# optical_encoder.net
KiCad netlist of a schematic drawn in EAGLE
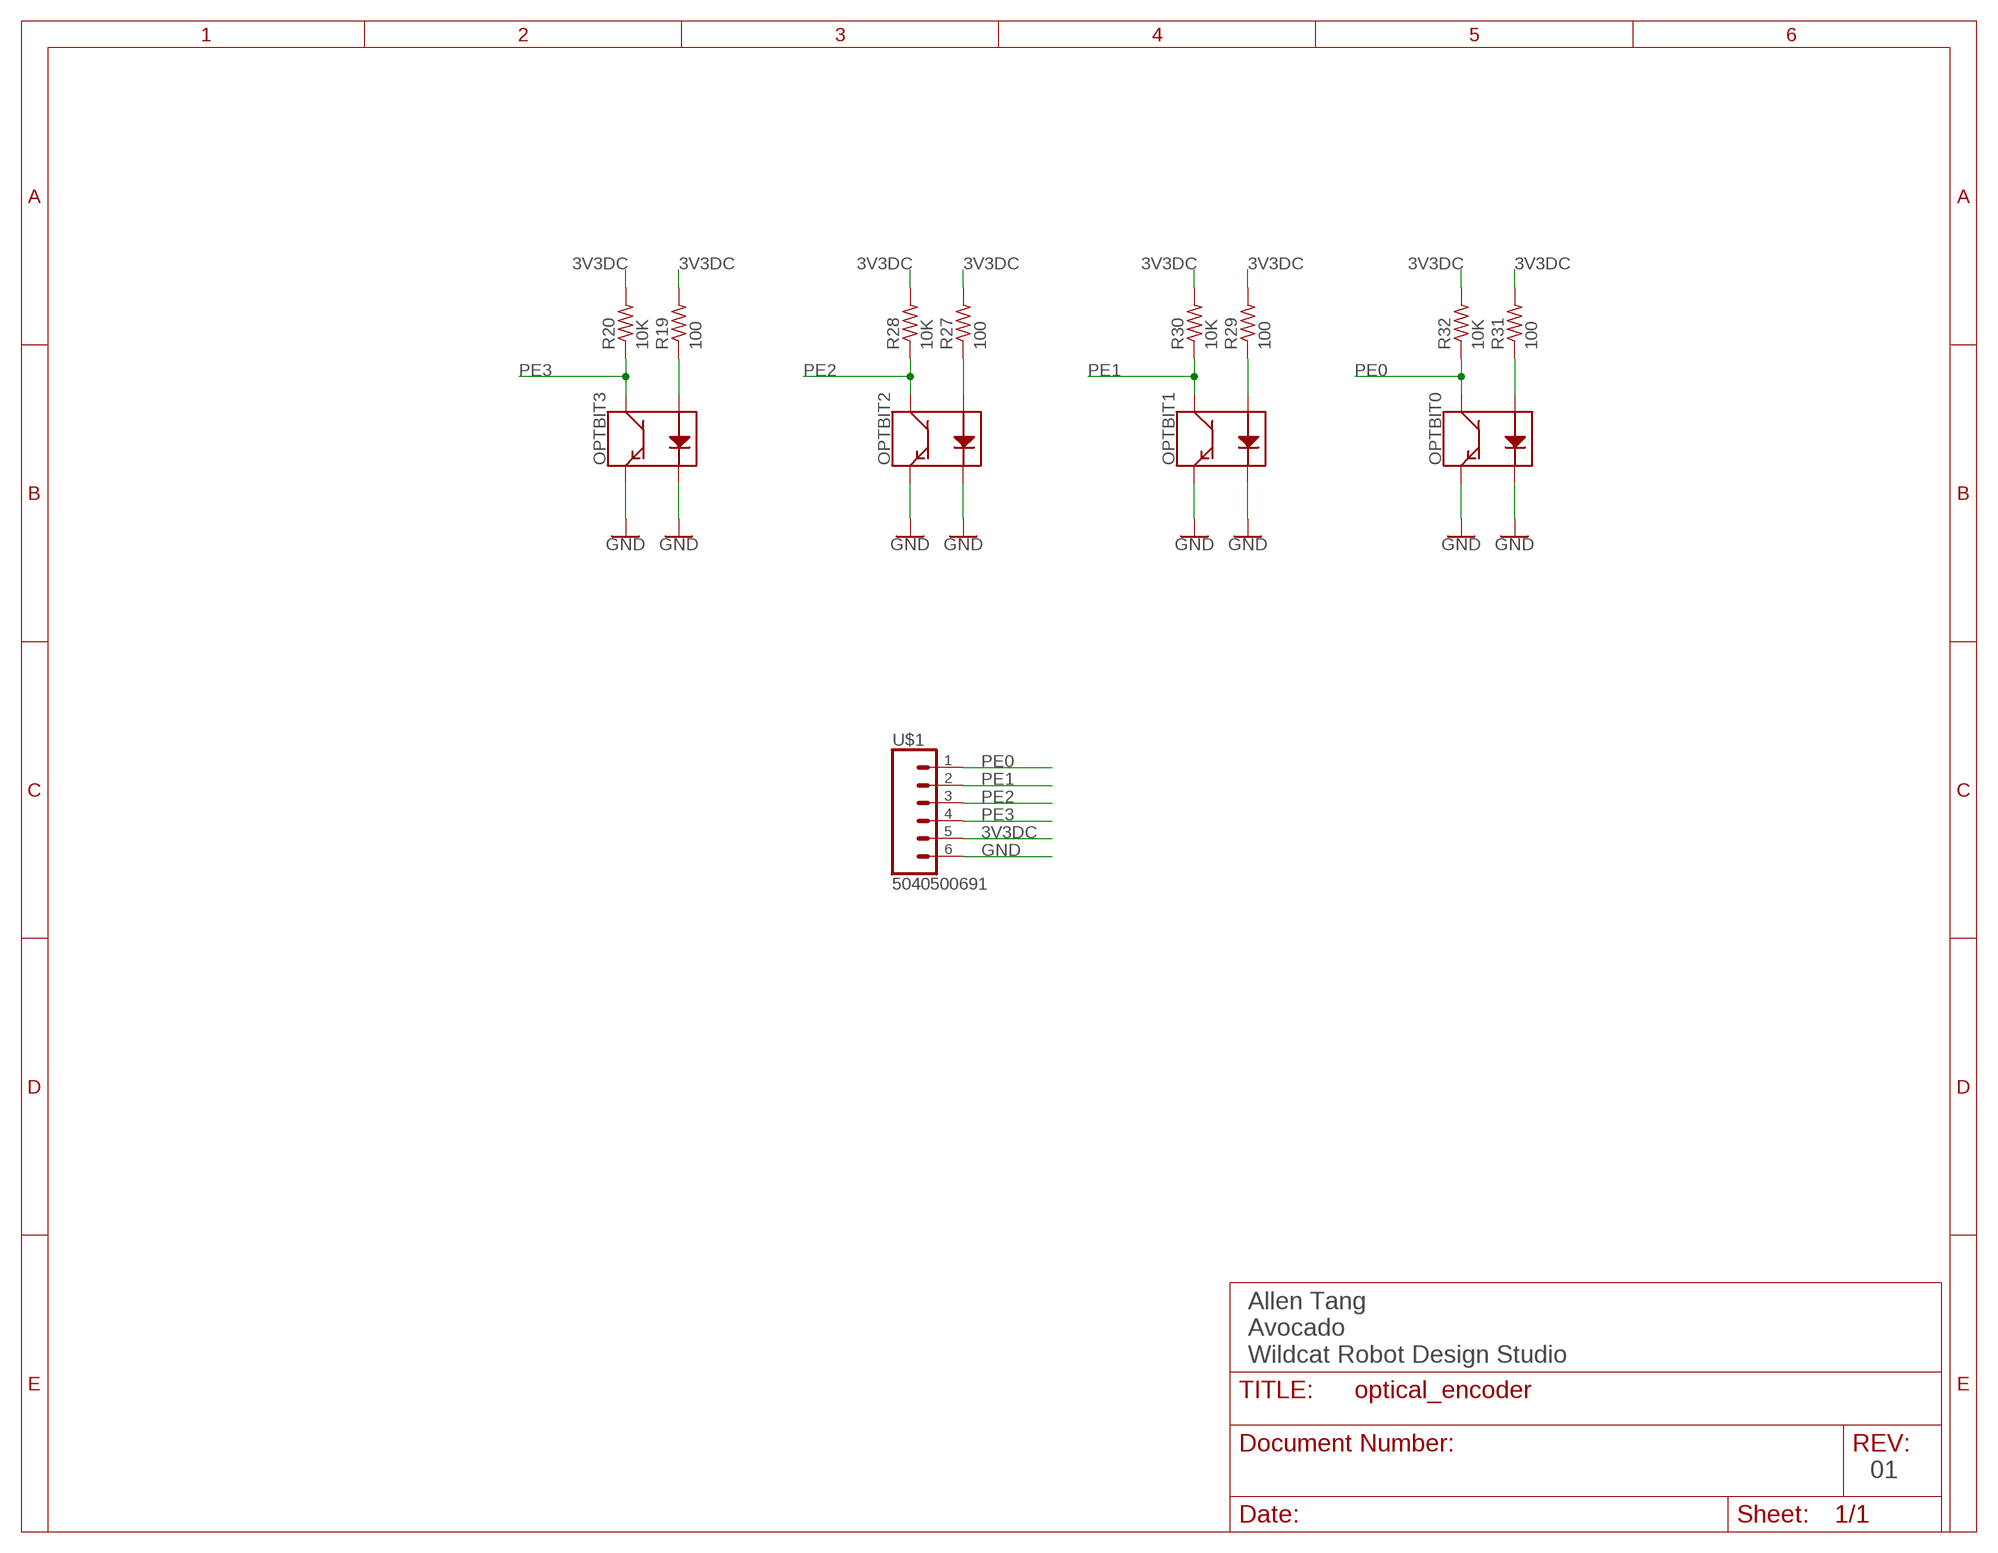
[diagram p0: schematic, sheet 1]

(export (version "E")
  (design (tool "Eeschema 10.0.6"))
  (components
    (comp (ref "OPTBIT0")
      (value "QRE1113")
      (footprint "eagle-import:QRE1113")
      (libsource (lib "eagle-import") (part "QRE1113"))
    )
    (comp (ref "OPTBIT1")
      (value "QRE1113")
      (footprint "eagle-import:QRE1113")
      (libsource (lib "eagle-import") (part "QRE1113"))
    )
    (comp (ref "OPTBIT2")
      (value "QRE1113")
      (footprint "eagle-import:QRE1113")
      (libsource (lib "eagle-import") (part "QRE1113"))
    )
    (comp (ref "OPTBIT3")
      (value "QRE1113")
      (footprint "eagle-import:QRE1113")
      (libsource (lib "eagle-import") (part "QRE1113"))
    )
    (comp (ref "R19")
      (value "100")
      (footprint "eagle-import:R0402")
      (libsource (lib "eagle-import") (part "R-US_R0402"))
    )
    (comp (ref "R20")
      (value "10K")
      (footprint "eagle-import:R0402")
      (libsource (lib "eagle-import") (part "R-US_R0402"))
    )
    (comp (ref "R27")
      (value "100")
      (footprint "eagle-import:R0402")
      (libsource (lib "eagle-import") (part "R-US_R0402"))
    )
    (comp (ref "R28")
      (value "10K")
      (footprint "eagle-import:R0402")
      (libsource (lib "eagle-import") (part "R-US_R0402"))
    )
    (comp (ref "R29")
      (value "100")
      (footprint "eagle-import:R0402")
      (libsource (lib "eagle-import") (part "R-US_R0402"))
    )
    (comp (ref "R30")
      (value "10K")
      (footprint "eagle-import:R0402")
      (libsource (lib "eagle-import") (part "R-US_R0402"))
    )
    (comp (ref "R31")
      (value "100")
      (footprint "eagle-import:R0402")
      (libsource (lib "eagle-import") (part "R-US_R0402"))
    )
    (comp (ref "R32")
      (value "10K")
      (footprint "eagle-import:R0402")
      (libsource (lib "eagle-import") (part "R-US_R0402"))
    )
    (comp (ref "U$1")
      (value "5040500691")
      (footprint "eagle-import:5040500691")
      (libsource (lib "eagle-import") (part "5040500691"))
    )
  )
  (nets
    (net (code "1") (name "/3V3DC") (class "Default")
      (node (ref "R19") (pin "2") (pinfunction "2_2") (pintype "passive"))
      (node (ref "R20") (pin "2") (pinfunction "2_2") (pintype "passive"))
      (node (ref "R27") (pin "2") (pinfunction "2_2") (pintype "passive"))
      (node (ref "R28") (pin "2") (pinfunction "2_2") (pintype "passive"))
      (node (ref "R29") (pin "2") (pinfunction "2_2") (pintype "passive"))
      (node (ref "R30") (pin "2") (pinfunction "2_2") (pintype "passive"))
      (node (ref "R31") (pin "2") (pinfunction "2_2") (pintype "passive"))
      (node (ref "R32") (pin "2") (pinfunction "2_2") (pintype "passive"))
      (node (ref "U$1") (pin "5") (pinfunction "5_5") (pintype "passive"))
    )
    (net (code "2") (name "/PE0") (class "Default")
      (node (ref "OPTBIT0") (pin "3") (pinfunction "C_3") (pintype "bidirectional"))
      (node (ref "R32") (pin "1") (pinfunction "1_1") (pintype "passive"))
      (node (ref "U$1") (pin "1") (pinfunction "1_1") (pintype "passive"))
    )
    (net (code "3") (name "/PE1") (class "Default")
      (node (ref "OPTBIT1") (pin "3") (pinfunction "C_3") (pintype "bidirectional"))
      (node (ref "R30") (pin "1") (pinfunction "1_1") (pintype "passive"))
      (node (ref "U$1") (pin "2") (pinfunction "2_2") (pintype "passive"))
    )
    (net (code "4") (name "/PE2") (class "Default")
      (node (ref "OPTBIT2") (pin "3") (pinfunction "C_3") (pintype "bidirectional"))
      (node (ref "R28") (pin "1") (pinfunction "1_1") (pintype "passive"))
      (node (ref "U$1") (pin "3") (pinfunction "3_3") (pintype "passive"))
    )
    (net (code "5") (name "/PE3") (class "Default")
      (node (ref "OPTBIT3") (pin "3") (pinfunction "C_3") (pintype "bidirectional"))
      (node (ref "R20") (pin "1") (pinfunction "1_1") (pintype "passive"))
      (node (ref "U$1") (pin "4") (pinfunction "4_4") (pintype "passive"))
    )
    (net (code "6") (name "GND") (class "Default")
      (node (ref "OPTBIT0") (pin "2") (pinfunction "K_2") (pintype "bidirectional"))
      (node (ref "OPTBIT0") (pin "4") (pinfunction "E_4") (pintype "bidirectional"))
      (node (ref "OPTBIT1") (pin "2") (pinfunction "K_2") (pintype "bidirectional"))
      (node (ref "OPTBIT1") (pin "4") (pinfunction "E_4") (pintype "bidirectional"))
      (node (ref "OPTBIT2") (pin "2") (pinfunction "K_2") (pintype "bidirectional"))
      (node (ref "OPTBIT2") (pin "4") (pinfunction "E_4") (pintype "bidirectional"))
      (node (ref "OPTBIT3") (pin "2") (pinfunction "K_2") (pintype "bidirectional"))
      (node (ref "OPTBIT3") (pin "4") (pinfunction "E_4") (pintype "bidirectional"))
      (node (ref "U$1") (pin "6") (pinfunction "6_6") (pintype "passive"))
    )
    (net (code "7") (name "Net-(OPTBIT0-A)") (class "Default")
      (node (ref "OPTBIT0") (pin "1") (pinfunction "A_1") (pintype "bidirectional"))
      (node (ref "R31") (pin "1") (pinfunction "1_1") (pintype "passive"))
    )
    (net (code "8") (name "Net-(OPTBIT1-A)") (class "Default")
      (node (ref "OPTBIT1") (pin "1") (pinfunction "A_1") (pintype "bidirectional"))
      (node (ref "R29") (pin "1") (pinfunction "1_1") (pintype "passive"))
    )
    (net (code "9") (name "Net-(OPTBIT2-A)") (class "Default")
      (node (ref "OPTBIT2") (pin "1") (pinfunction "A_1") (pintype "bidirectional"))
      (node (ref "R27") (pin "1") (pinfunction "1_1") (pintype "passive"))
    )
    (net (code "10") (name "Net-(OPTBIT3-A)") (class "Default")
      (node (ref "OPTBIT3") (pin "1") (pinfunction "A_1") (pintype "bidirectional"))
      (node (ref "R19") (pin "1") (pinfunction "1_1") (pintype "passive"))
    )
  )
)
